# Fpga.net
KiCad netlist of a schematic drawn in Altium Designer
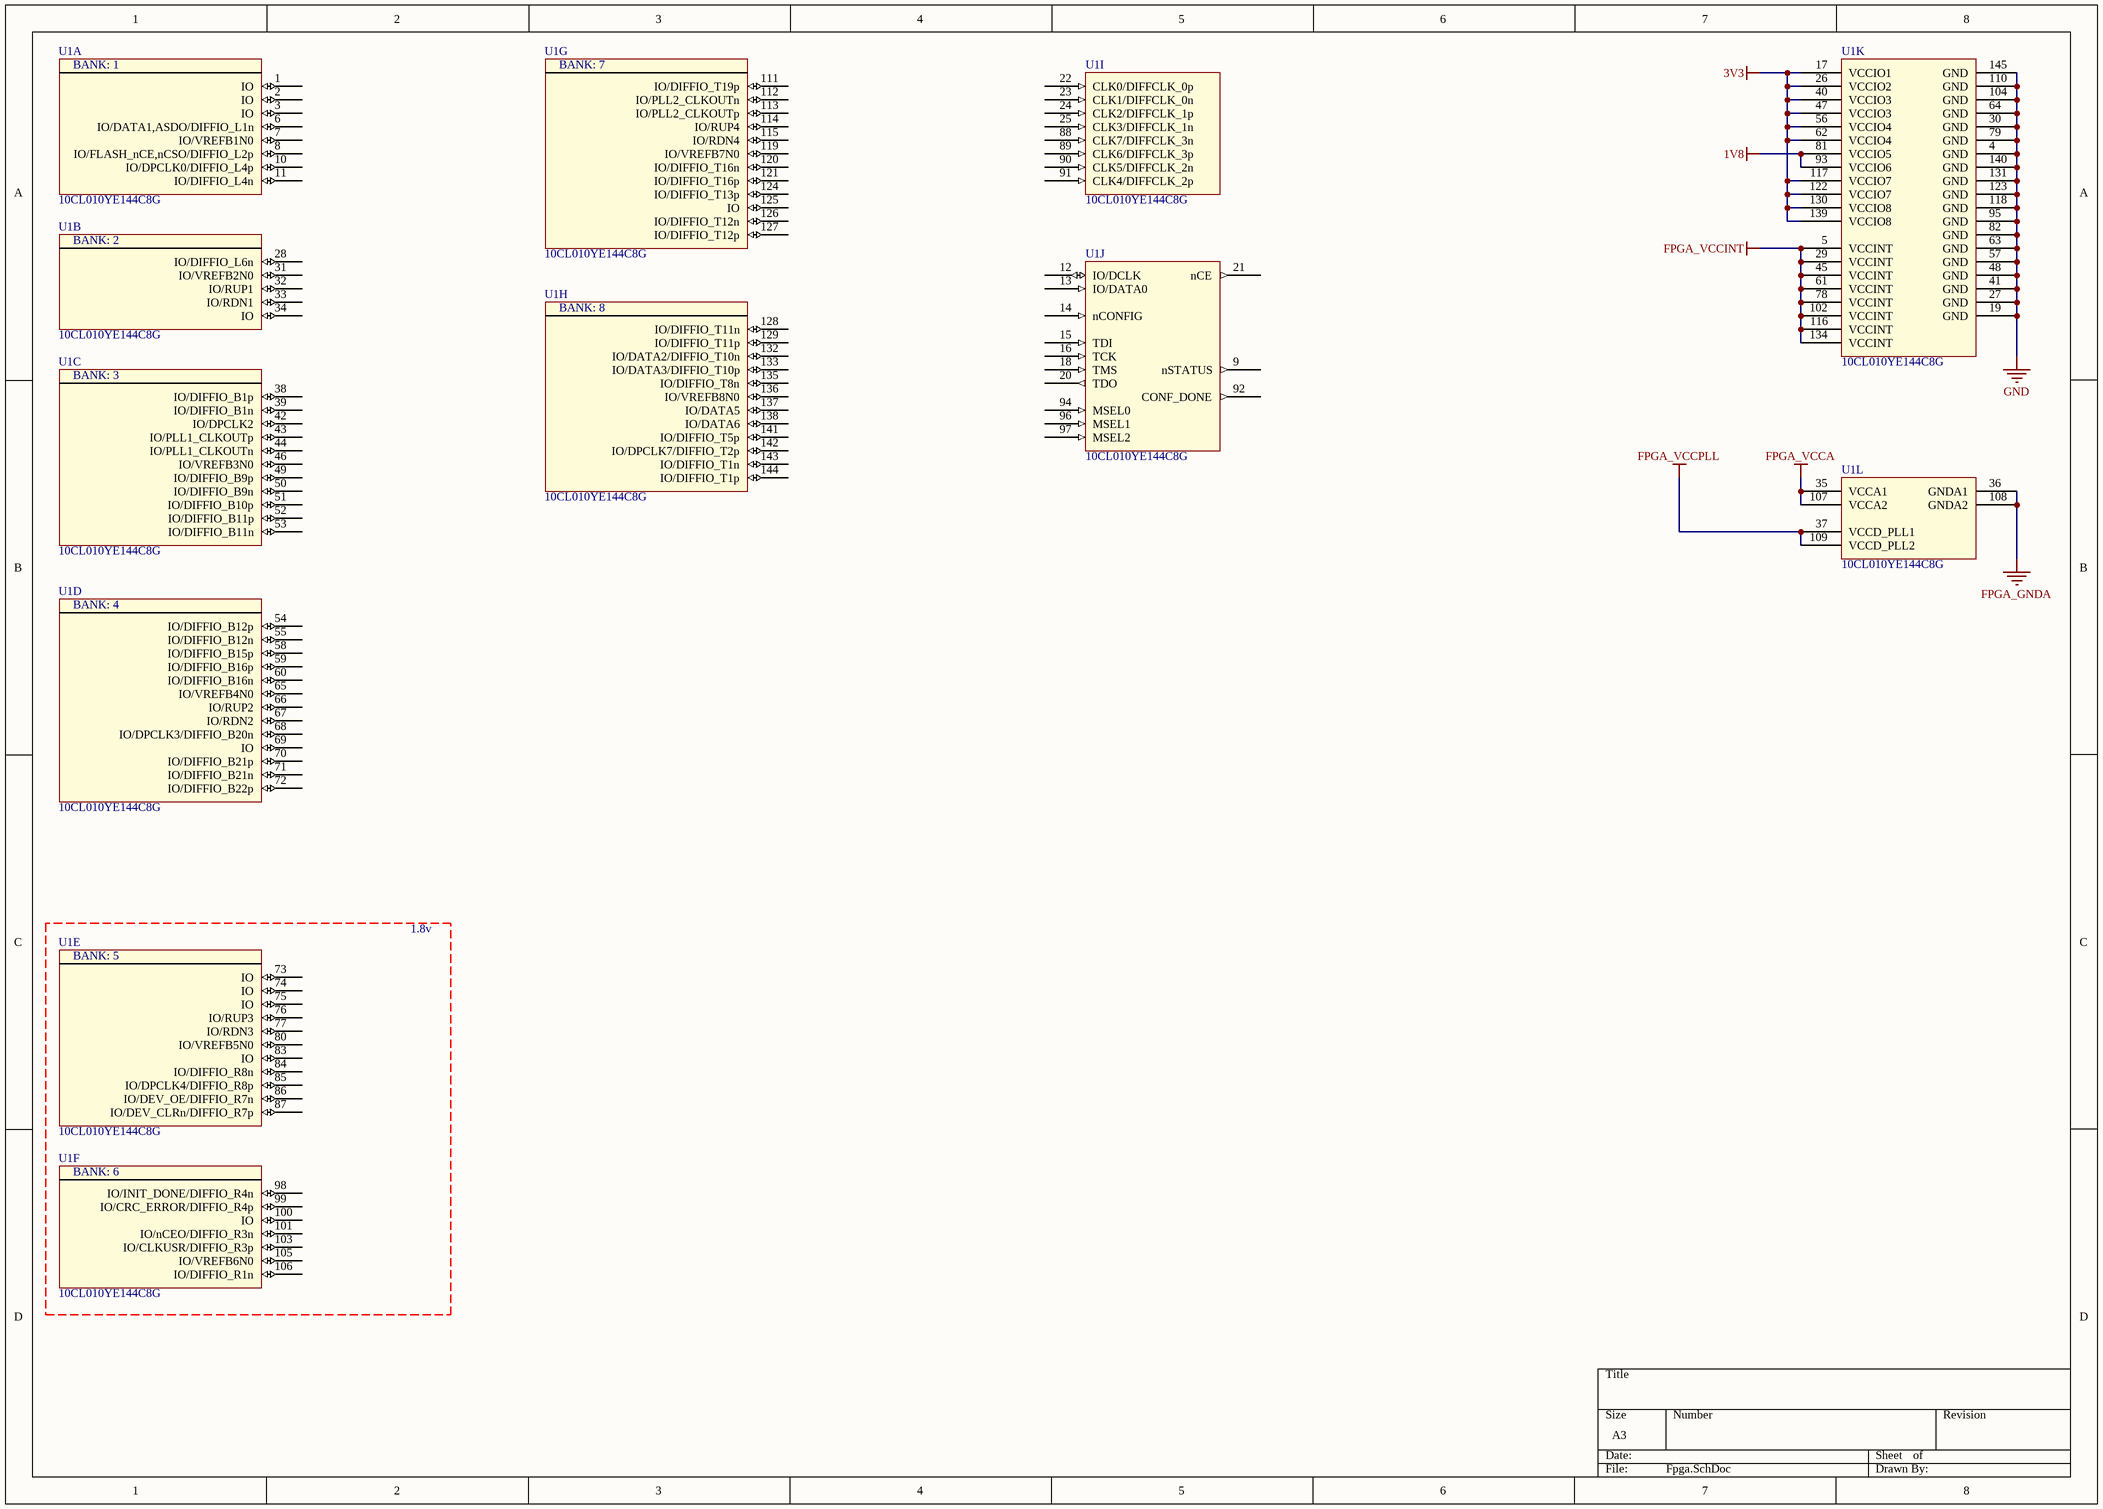
[diagram p0: Fpga.SchDoc]

(export (version "E")
  (design (tool "Eeschema 10.0.6"))
  (components
    (comp (ref "U1")
      (value "10CL010YE144C8G")
      (footprint "Altera TQFP 50P 22X22 145N")
      (description "Intel® Cyclone®10 10CL010 Device")
      (libsource (lib "Schlib") (part "10CL010YE144C8G"))
    )
  )
  (nets
    (net (code "1") (name "1V8") (class "Default")
      (node (ref "U1") (pin "81") (pinfunction "VCCIO5_81") (pintype "power_in"))
      (node (ref "U1") (pin "93") (pinfunction "VCCIO6_93") (pintype "power_in"))
    )
    (net (code "2") (name "3V3") (class "Default")
      (node (ref "U1") (pin "117") (pinfunction "VCCIO7_117") (pintype "power_in"))
      (node (ref "U1") (pin "122") (pinfunction "VCCIO7_122") (pintype "power_in"))
      (node (ref "U1") (pin "130") (pinfunction "VCCIO8_130") (pintype "power_in"))
      (node (ref "U1") (pin "139") (pinfunction "VCCIO8_139") (pintype "power_in"))
      (node (ref "U1") (pin "17") (pinfunction "VCCIO1_17") (pintype "power_in"))
      (node (ref "U1") (pin "26") (pinfunction "VCCIO2_26") (pintype "power_in"))
      (node (ref "U1") (pin "40") (pinfunction "VCCIO3_40") (pintype "power_in"))
      (node (ref "U1") (pin "47") (pinfunction "VCCIO3_47") (pintype "power_in"))
      (node (ref "U1") (pin "56") (pinfunction "VCCIO4_56") (pintype "power_in"))
      (node (ref "U1") (pin "62") (pinfunction "VCCIO4_62") (pintype "power_in"))
    )
    (net (code "3") (name "FPGA_GNDA") (class "Default")
      (node (ref "U1") (pin "108") (pinfunction "GNDA2_108") (pintype "power_in"))
      (node (ref "U1") (pin "36") (pinfunction "GNDA1_36") (pintype "power_in"))
    )
    (net (code "4") (name "FPGA_VCCA") (class "Default")
      (node (ref "U1") (pin "107") (pinfunction "VCCA2_107") (pintype "power_in"))
      (node (ref "U1") (pin "35") (pinfunction "VCCA1_35") (pintype "power_in"))
    )
    (net (code "5") (name "FPGA_VCCINT") (class "Default")
      (node (ref "U1") (pin "102") (pinfunction "VCCINT_102") (pintype "power_in"))
      (node (ref "U1") (pin "116") (pinfunction "VCCINT_116") (pintype "power_in"))
      (node (ref "U1") (pin "134") (pinfunction "VCCINT_134") (pintype "power_in"))
      (node (ref "U1") (pin "29") (pinfunction "VCCINT_29") (pintype "power_in"))
      (node (ref "U1") (pin "45") (pinfunction "VCCINT_45") (pintype "power_in"))
      (node (ref "U1") (pin "5") (pinfunction "VCCINT_5") (pintype "power_in"))
      (node (ref "U1") (pin "61") (pinfunction "VCCINT_61") (pintype "power_in"))
      (node (ref "U1") (pin "78") (pinfunction "VCCINT_78") (pintype "power_in"))
    )
    (net (code "6") (name "FPGA_VCCPLL") (class "Default")
      (node (ref "U1") (pin "109") (pinfunction "VCCD_PLL2_109") (pintype "power_in"))
      (node (ref "U1") (pin "37") (pinfunction "VCCD_PLL1_37") (pintype "power_in"))
    )
    (net (code "7") (name "GND") (class "Default")
      (node (ref "U1") (pin "104") (pinfunction "GND_104") (pintype "power_in"))
      (node (ref "U1") (pin "110") (pinfunction "GND_110") (pintype "power_in"))
      (node (ref "U1") (pin "118") (pinfunction "GND_118") (pintype "power_in"))
      (node (ref "U1") (pin "123") (pinfunction "GND_123") (pintype "power_in"))
      (node (ref "U1") (pin "131") (pinfunction "GND_131") (pintype "power_in"))
      (node (ref "U1") (pin "140") (pinfunction "GND_140") (pintype "power_in"))
      (node (ref "U1") (pin "145") (pinfunction "GND_145") (pintype "power_in"))
      (node (ref "U1") (pin "19") (pinfunction "GND_19") (pintype "power_in"))
      (node (ref "U1") (pin "27") (pinfunction "GND_27") (pintype "power_in"))
      (node (ref "U1") (pin "30") (pinfunction "GND_30") (pintype "power_in"))
      (node (ref "U1") (pin "4") (pinfunction "GND_4") (pintype "power_in"))
      (node (ref "U1") (pin "41") (pinfunction "GND_41") (pintype "power_in"))
      (node (ref "U1") (pin "48") (pinfunction "GND_48") (pintype "power_in"))
      (node (ref "U1") (pin "57") (pinfunction "GND_57") (pintype "power_in"))
      (node (ref "U1") (pin "63") (pinfunction "GND_63") (pintype "power_in"))
      (node (ref "U1") (pin "64") (pinfunction "GND_64") (pintype "power_in"))
      (node (ref "U1") (pin "79") (pinfunction "GND_79") (pintype "power_in"))
      (node (ref "U1") (pin "82") (pinfunction "GND_82") (pintype "power_in"))
      (node (ref "U1") (pin "95") (pinfunction "GND_95") (pintype "power_in"))
    )
    (net (code "8") (name "unconnected-(U1A-IO-Pad1)") (class "Default")
      (node (ref "U1") (pin "1") (pinfunction "IO_1") (pintype "bidirectional"))
    )
    (net (code "9") (name "unconnected-(U1A-IO-Pad2)") (class "Default")
      (node (ref "U1") (pin "2") (pinfunction "IO_2") (pintype "bidirectional"))
    )
    (net (code "10") (name "unconnected-(U1A-IO-Pad3)") (class "Default")
      (node (ref "U1") (pin "3") (pinfunction "IO_3") (pintype "bidirectional"))
    )
    (net (code "11") (name "unconnected-(U1A-IO{slash}DATA1,ASDO{slash}DIFFIO_L1n-Pad6)") (class "Default")
      (node (ref "U1") (pin "6") (pinfunction "IO/DATA1,ASDO/DIFFIO_L1n_6") (pintype "bidirectional"))
    )
    (net (code "12") (name "unconnected-(U1A-IO{slash}DIFFIO_L4n-Pad11)") (class "Default")
      (node (ref "U1") (pin "11") (pinfunction "IO/DIFFIO_L4n_11") (pintype "bidirectional"))
    )
    (net (code "13") (name "unconnected-(U1A-IO{slash}DPCLK0{slash}DIFFIO_L4p-Pad10)") (class "Default")
      (node (ref "U1") (pin "10") (pinfunction "IO/DPCLK0/DIFFIO_L4p_10") (pintype "bidirectional"))
    )
    (net (code "14") (name "unconnected-(U1A-IO{slash}FLASH_nCE,nCSO{slash}DIFFIO_L2p-Pad8)") (class "Default")
      (node (ref "U1") (pin "8") (pinfunction "IO/FLASH_nCE,nCSO/DIFFIO_L2p_8") (pintype "bidirectional"))
    )
    (net (code "15") (name "unconnected-(U1A-IO{slash}VREFB1N0-Pad7)") (class "Default")
      (node (ref "U1") (pin "7") (pinfunction "IO/VREFB1N0_7") (pintype "bidirectional"))
    )
    (net (code "16") (name "unconnected-(U1B-IO-Pad34)") (class "Default")
      (node (ref "U1") (pin "34") (pinfunction "IO_34") (pintype "bidirectional"))
    )
    (net (code "17") (name "unconnected-(U1B-IO{slash}DIFFIO_L6n-Pad28)") (class "Default")
      (node (ref "U1") (pin "28") (pinfunction "IO/DIFFIO_L6n_28") (pintype "bidirectional"))
    )
    (net (code "18") (name "unconnected-(U1B-IO{slash}RDN1-Pad33)") (class "Default")
      (node (ref "U1") (pin "33") (pinfunction "IO/RDN1_33") (pintype "bidirectional"))
    )
    (net (code "19") (name "unconnected-(U1B-IO{slash}RUP1-Pad32)") (class "Default")
      (node (ref "U1") (pin "32") (pinfunction "IO/RUP1_32") (pintype "bidirectional"))
    )
    (net (code "20") (name "unconnected-(U1B-IO{slash}VREFB2N0-Pad31)") (class "Default")
      (node (ref "U1") (pin "31") (pinfunction "IO/VREFB2N0_31") (pintype "bidirectional"))
    )
    (net (code "21") (name "unconnected-(U1C-IO{slash}DIFFIO_B1n-Pad39)") (class "Default")
      (node (ref "U1") (pin "39") (pinfunction "IO/DIFFIO_B1n_39") (pintype "bidirectional"))
    )
    (net (code "22") (name "unconnected-(U1C-IO{slash}DIFFIO_B1p-Pad38)") (class "Default")
      (node (ref "U1") (pin "38") (pinfunction "IO/DIFFIO_B1p_38") (pintype "bidirectional"))
    )
    (net (code "23") (name "unconnected-(U1C-IO{slash}DIFFIO_B9n-Pad50)") (class "Default")
      (node (ref "U1") (pin "50") (pinfunction "IO/DIFFIO_B9n_50") (pintype "bidirectional"))
    )
    (net (code "24") (name "unconnected-(U1C-IO{slash}DIFFIO_B9p-Pad49)") (class "Default")
      (node (ref "U1") (pin "49") (pinfunction "IO/DIFFIO_B9p_49") (pintype "bidirectional"))
    )
    (net (code "25") (name "unconnected-(U1C-IO{slash}DIFFIO_B10p-Pad51)") (class "Default")
      (node (ref "U1") (pin "51") (pinfunction "IO/DIFFIO_B10p_51") (pintype "bidirectional"))
    )
    (net (code "26") (name "unconnected-(U1C-IO{slash}DIFFIO_B11n-Pad53)") (class "Default")
      (node (ref "U1") (pin "53") (pinfunction "IO/DIFFIO_B11n_53") (pintype "bidirectional"))
    )
    (net (code "27") (name "unconnected-(U1C-IO{slash}DIFFIO_B11p-Pad52)") (class "Default")
      (node (ref "U1") (pin "52") (pinfunction "IO/DIFFIO_B11p_52") (pintype "bidirectional"))
    )
    (net (code "28") (name "unconnected-(U1C-IO{slash}DPCLK2-Pad42)") (class "Default")
      (node (ref "U1") (pin "42") (pinfunction "IO/DPCLK2_42") (pintype "bidirectional"))
    )
    (net (code "29") (name "unconnected-(U1C-IO{slash}PLL1_CLKOUTn-Pad44)") (class "Default")
      (node (ref "U1") (pin "44") (pinfunction "IO/PLL1_CLKOUTn_44") (pintype "bidirectional"))
    )
    (net (code "30") (name "unconnected-(U1C-IO{slash}PLL1_CLKOUTp-Pad43)") (class "Default")
      (node (ref "U1") (pin "43") (pinfunction "IO/PLL1_CLKOUTp_43") (pintype "bidirectional"))
    )
    (net (code "31") (name "unconnected-(U1C-IO{slash}VREFB3N0-Pad46)") (class "Default")
      (node (ref "U1") (pin "46") (pinfunction "IO/VREFB3N0_46") (pintype "bidirectional"))
    )
    (net (code "32") (name "unconnected-(U1D-IO-Pad69)") (class "Default")
      (node (ref "U1") (pin "69") (pinfunction "IO_69") (pintype "bidirectional"))
    )
    (net (code "33") (name "unconnected-(U1D-IO{slash}DIFFIO_B12n-Pad55)") (class "Default")
      (node (ref "U1") (pin "55") (pinfunction "IO/DIFFIO_B12n_55") (pintype "bidirectional"))
    )
    (net (code "34") (name "unconnected-(U1D-IO{slash}DIFFIO_B12p-Pad54)") (class "Default")
      (node (ref "U1") (pin "54") (pinfunction "IO/DIFFIO_B12p_54") (pintype "bidirectional"))
    )
    (net (code "35") (name "unconnected-(U1D-IO{slash}DIFFIO_B15p-Pad58)") (class "Default")
      (node (ref "U1") (pin "58") (pinfunction "IO/DIFFIO_B15p_58") (pintype "bidirectional"))
    )
    (net (code "36") (name "unconnected-(U1D-IO{slash}DIFFIO_B16n-Pad60)") (class "Default")
      (node (ref "U1") (pin "60") (pinfunction "IO/DIFFIO_B16n_60") (pintype "bidirectional"))
    )
    (net (code "37") (name "unconnected-(U1D-IO{slash}DIFFIO_B16p-Pad59)") (class "Default")
      (node (ref "U1") (pin "59") (pinfunction "IO/DIFFIO_B16p_59") (pintype "bidirectional"))
    )
    (net (code "38") (name "unconnected-(U1D-IO{slash}DIFFIO_B21n-Pad71)") (class "Default")
      (node (ref "U1") (pin "71") (pinfunction "IO/DIFFIO_B21n_71") (pintype "bidirectional"))
    )
    (net (code "39") (name "unconnected-(U1D-IO{slash}DIFFIO_B21p-Pad70)") (class "Default")
      (node (ref "U1") (pin "70") (pinfunction "IO/DIFFIO_B21p_70") (pintype "bidirectional"))
    )
    (net (code "40") (name "unconnected-(U1D-IO{slash}DIFFIO_B22p-Pad72)") (class "Default")
      (node (ref "U1") (pin "72") (pinfunction "IO/DIFFIO_B22p_72") (pintype "bidirectional"))
    )
    (net (code "41") (name "unconnected-(U1D-IO{slash}DPCLK3{slash}DIFFIO_B20n-Pad68)") (class "Default")
      (node (ref "U1") (pin "68") (pinfunction "IO/DPCLK3/DIFFIO_B20n_68") (pintype "bidirectional"))
    )
    (net (code "42") (name "unconnected-(U1D-IO{slash}RDN2-Pad67)") (class "Default")
      (node (ref "U1") (pin "67") (pinfunction "IO/RDN2_67") (pintype "bidirectional"))
    )
    (net (code "43") (name "unconnected-(U1D-IO{slash}RUP2-Pad66)") (class "Default")
      (node (ref "U1") (pin "66") (pinfunction "IO/RUP2_66") (pintype "bidirectional"))
    )
    (net (code "44") (name "unconnected-(U1D-IO{slash}VREFB4N0-Pad65)") (class "Default")
      (node (ref "U1") (pin "65") (pinfunction "IO/VREFB4N0_65") (pintype "bidirectional"))
    )
    (net (code "45") (name "unconnected-(U1E-IO-Pad73)") (class "Default")
      (node (ref "U1") (pin "73") (pinfunction "IO_73") (pintype "bidirectional"))
    )
    (net (code "46") (name "unconnected-(U1E-IO-Pad74)") (class "Default")
      (node (ref "U1") (pin "74") (pinfunction "IO_74") (pintype "bidirectional"))
    )
    (net (code "47") (name "unconnected-(U1E-IO-Pad75)") (class "Default")
      (node (ref "U1") (pin "75") (pinfunction "IO_75") (pintype "bidirectional"))
    )
    (net (code "48") (name "unconnected-(U1E-IO-Pad83)") (class "Default")
      (node (ref "U1") (pin "83") (pinfunction "IO_83") (pintype "bidirectional"))
    )
    (net (code "49") (name "unconnected-(U1E-IO{slash}DEV_CLRn{slash}DIFFIO_R7p-Pad87)") (class "Default")
      (node (ref "U1") (pin "87") (pinfunction "IO/DEV_CLRn/DIFFIO_R7p_87") (pintype "bidirectional"))
    )
    (net (code "50") (name "unconnected-(U1E-IO{slash}DEV_OE{slash}DIFFIO_R7n-Pad86)") (class "Default")
      (node (ref "U1") (pin "86") (pinfunction "IO/DEV_OE/DIFFIO_R7n_86") (pintype "bidirectional"))
    )
    (net (code "51") (name "unconnected-(U1E-IO{slash}DIFFIO_R8n-Pad84)") (class "Default")
      (node (ref "U1") (pin "84") (pinfunction "IO/DIFFIO_R8n_84") (pintype "bidirectional"))
    )
    (net (code "52") (name "unconnected-(U1E-IO{slash}DPCLK4{slash}DIFFIO_R8p-Pad85)") (class "Default")
      (node (ref "U1") (pin "85") (pinfunction "IO/DPCLK4/DIFFIO_R8p_85") (pintype "bidirectional"))
    )
    (net (code "53") (name "unconnected-(U1E-IO{slash}RDN3-Pad77)") (class "Default")
      (node (ref "U1") (pin "77") (pinfunction "IO/RDN3_77") (pintype "bidirectional"))
    )
    (net (code "54") (name "unconnected-(U1E-IO{slash}RUP3-Pad76)") (class "Default")
      (node (ref "U1") (pin "76") (pinfunction "IO/RUP3_76") (pintype "bidirectional"))
    )
    (net (code "55") (name "unconnected-(U1E-IO{slash}VREFB5N0-Pad80)") (class "Default")
      (node (ref "U1") (pin "80") (pinfunction "IO/VREFB5N0_80") (pintype "bidirectional"))
    )
    (net (code "56") (name "unconnected-(U1F-IO-Pad100)") (class "Default")
      (node (ref "U1") (pin "100") (pinfunction "IO_100") (pintype "bidirectional"))
    )
    (net (code "57") (name "unconnected-(U1F-IO{slash}CLKUSR{slash}DIFFIO_R3p-Pad103)") (class "Default")
      (node (ref "U1") (pin "103") (pinfunction "IO/CLKUSR/DIFFIO_R3p_103") (pintype "bidirectional"))
    )
    (net (code "58") (name "unconnected-(U1F-IO{slash}CRC_ERROR{slash}DIFFIO_R4p-Pad99)") (class "Default")
      (node (ref "U1") (pin "99") (pinfunction "IO/CRC_ERROR/DIFFIO_R4p_99") (pintype "bidirectional"))
    )
    (net (code "59") (name "unconnected-(U1F-IO{slash}DIFFIO_R1n-Pad106)") (class "Default")
      (node (ref "U1") (pin "106") (pinfunction "IO/DIFFIO_R1n_106") (pintype "bidirectional"))
    )
    (net (code "60") (name "unconnected-(U1F-IO{slash}INIT_DONE{slash}DIFFIO_R4n-Pad98)") (class "Default")
      (node (ref "U1") (pin "98") (pinfunction "IO/INIT_DONE/DIFFIO_R4n_98") (pintype "bidirectional"))
    )
    (net (code "61") (name "unconnected-(U1F-IO{slash}VREFB6N0-Pad105)") (class "Default")
      (node (ref "U1") (pin "105") (pinfunction "IO/VREFB6N0_105") (pintype "bidirectional"))
    )
    (net (code "62") (name "unconnected-(U1F-IO{slash}nCEO{slash}DIFFIO_R3n-Pad101)") (class "Default")
      (node (ref "U1") (pin "101") (pinfunction "IO/nCEO/DIFFIO_R3n_101") (pintype "bidirectional"))
    )
    (net (code "63") (name "unconnected-(U1G-IO-Pad125)") (class "Default")
      (node (ref "U1") (pin "125") (pinfunction "IO_125") (pintype "bidirectional"))
    )
    (net (code "64") (name "unconnected-(U1G-IO{slash}DIFFIO_T12n-Pad126)") (class "Default")
      (node (ref "U1") (pin "126") (pinfunction "IO/DIFFIO_T12n_126") (pintype "bidirectional"))
    )
    (net (code "65") (name "unconnected-(U1G-IO{slash}DIFFIO_T12p-Pad127)") (class "Default")
      (node (ref "U1") (pin "127") (pinfunction "IO/DIFFIO_T12p_127") (pintype "bidirectional"))
    )
    (net (code "66") (name "unconnected-(U1G-IO{slash}DIFFIO_T13p-Pad124)") (class "Default")
      (node (ref "U1") (pin "124") (pinfunction "IO/DIFFIO_T13p_124") (pintype "bidirectional"))
    )
    (net (code "67") (name "unconnected-(U1G-IO{slash}DIFFIO_T16n-Pad120)") (class "Default")
      (node (ref "U1") (pin "120") (pinfunction "IO/DIFFIO_T16n_120") (pintype "bidirectional"))
    )
    (net (code "68") (name "unconnected-(U1G-IO{slash}DIFFIO_T16p-Pad121)") (class "Default")
      (node (ref "U1") (pin "121") (pinfunction "IO/DIFFIO_T16p_121") (pintype "bidirectional"))
    )
    (net (code "69") (name "unconnected-(U1G-IO{slash}DIFFIO_T19p-Pad111)") (class "Default")
      (node (ref "U1") (pin "111") (pinfunction "IO/DIFFIO_T19p_111") (pintype "bidirectional"))
    )
    (net (code "70") (name "unconnected-(U1G-IO{slash}PLL2_CLKOUTn-Pad112)") (class "Default")
      (node (ref "U1") (pin "112") (pinfunction "IO/PLL2_CLKOUTn_112") (pintype "bidirectional"))
    )
    (net (code "71") (name "unconnected-(U1G-IO{slash}PLL2_CLKOUTp-Pad113)") (class "Default")
      (node (ref "U1") (pin "113") (pinfunction "IO/PLL2_CLKOUTp_113") (pintype "bidirectional"))
    )
    (net (code "72") (name "unconnected-(U1G-IO{slash}RDN4-Pad115)") (class "Default")
      (node (ref "U1") (pin "115") (pinfunction "IO/RDN4_115") (pintype "bidirectional"))
    )
    (net (code "73") (name "unconnected-(U1G-IO{slash}RUP4-Pad114)") (class "Default")
      (node (ref "U1") (pin "114") (pinfunction "IO/RUP4_114") (pintype "bidirectional"))
    )
    (net (code "74") (name "unconnected-(U1G-IO{slash}VREFB7N0-Pad119)") (class "Default")
      (node (ref "U1") (pin "119") (pinfunction "IO/VREFB7N0_119") (pintype "bidirectional"))
    )
    (net (code "75") (name "unconnected-(U1H-IO{slash}DATA2{slash}DIFFIO_T10n-Pad132)") (class "Default")
      (node (ref "U1") (pin "132") (pinfunction "IO/DATA2/DIFFIO_T10n_132") (pintype "bidirectional"))
    )
    (net (code "76") (name "unconnected-(U1H-IO{slash}DATA3{slash}DIFFIO_T10p-Pad133)") (class "Default")
      (node (ref "U1") (pin "133") (pinfunction "IO/DATA3/DIFFIO_T10p_133") (pintype "bidirectional"))
    )
    (net (code "77") (name "unconnected-(U1H-IO{slash}DATA5-Pad137)") (class "Default")
      (node (ref "U1") (pin "137") (pinfunction "IO/DATA5_137") (pintype "bidirectional"))
    )
    (net (code "78") (name "unconnected-(U1H-IO{slash}DATA6-Pad138)") (class "Default")
      (node (ref "U1") (pin "138") (pinfunction "IO/DATA6_138") (pintype "bidirectional"))
    )
    (net (code "79") (name "unconnected-(U1H-IO{slash}DIFFIO_T1n-Pad143)") (class "Default")
      (node (ref "U1") (pin "143") (pinfunction "IO/DIFFIO_T1n_143") (pintype "bidirectional"))
    )
    (net (code "80") (name "unconnected-(U1H-IO{slash}DIFFIO_T1p-Pad144)") (class "Default")
      (node (ref "U1") (pin "144") (pinfunction "IO/DIFFIO_T1p_144") (pintype "bidirectional"))
    )
    (net (code "81") (name "unconnected-(U1H-IO{slash}DIFFIO_T5p-Pad141)") (class "Default")
      (node (ref "U1") (pin "141") (pinfunction "IO/DIFFIO_T5p_141") (pintype "bidirectional"))
    )
    (net (code "82") (name "unconnected-(U1H-IO{slash}DIFFIO_T8n-Pad135)") (class "Default")
      (node (ref "U1") (pin "135") (pinfunction "IO/DIFFIO_T8n_135") (pintype "bidirectional"))
    )
    (net (code "83") (name "unconnected-(U1H-IO{slash}DIFFIO_T11n-Pad128)") (class "Default")
      (node (ref "U1") (pin "128") (pinfunction "IO/DIFFIO_T11n_128") (pintype "bidirectional"))
    )
    (net (code "84") (name "unconnected-(U1H-IO{slash}DIFFIO_T11p-Pad129)") (class "Default")
      (node (ref "U1") (pin "129") (pinfunction "IO/DIFFIO_T11p_129") (pintype "bidirectional"))
    )
    (net (code "85") (name "unconnected-(U1H-IO{slash}DPCLK7{slash}DIFFIO_T2p-Pad142)") (class "Default")
      (node (ref "U1") (pin "142") (pinfunction "IO/DPCLK7/DIFFIO_T2p_142") (pintype "bidirectional"))
    )
    (net (code "86") (name "unconnected-(U1H-IO{slash}VREFB8N0-Pad136)") (class "Default")
      (node (ref "U1") (pin "136") (pinfunction "IO/VREFB8N0_136") (pintype "bidirectional"))
    )
    (net (code "87") (name "unconnected-(U1I-CLK0{slash}DIFFCLK_0p-Pad22)") (class "Default")
      (node (ref "U1") (pin "22") (pinfunction "CLK0/DIFFCLK_0p_22") (pintype "input"))
    )
    (net (code "88") (name "unconnected-(U1I-CLK1{slash}DIFFCLK_0n-Pad23)") (class "Default")
      (node (ref "U1") (pin "23") (pinfunction "CLK1/DIFFCLK_0n_23") (pintype "input"))
    )
    (net (code "89") (name "unconnected-(U1I-CLK2{slash}DIFFCLK_1p-Pad24)") (class "Default")
      (node (ref "U1") (pin "24") (pinfunction "CLK2/DIFFCLK_1p_24") (pintype "input"))
    )
    (net (code "90") (name "unconnected-(U1I-CLK3{slash}DIFFCLK_1n-Pad25)") (class "Default")
      (node (ref "U1") (pin "25") (pinfunction "CLK3/DIFFCLK_1n_25") (pintype "input"))
    )
    (net (code "91") (name "unconnected-(U1I-CLK4{slash}DIFFCLK_2p-Pad91)") (class "Default")
      (node (ref "U1") (pin "91") (pinfunction "CLK4/DIFFCLK_2p_91") (pintype "input"))
    )
    (net (code "92") (name "unconnected-(U1I-CLK5{slash}DIFFCLK_2n-Pad90)") (class "Default")
      (node (ref "U1") (pin "90") (pinfunction "CLK5/DIFFCLK_2n_90") (pintype "input"))
    )
    (net (code "93") (name "unconnected-(U1I-CLK6{slash}DIFFCLK_3p-Pad89)") (class "Default")
      (node (ref "U1") (pin "89") (pinfunction "CLK6/DIFFCLK_3p_89") (pintype "input"))
    )
    (net (code "94") (name "unconnected-(U1I-CLK7{slash}DIFFCLK_3n-Pad88)") (class "Default")
      (node (ref "U1") (pin "88") (pinfunction "CLK7/DIFFCLK_3n_88") (pintype "input"))
    )
    (net (code "95") (name "unconnected-(U1J-CONF_DONE-Pad92)") (class "Default")
      (node (ref "U1") (pin "92") (pinfunction "CONF_DONE_92") (pintype "output"))
    )
    (net (code "96") (name "unconnected-(U1J-IO{slash}DATA0-Pad13)") (class "Default")
      (node (ref "U1") (pin "13") (pinfunction "IO/DATA0_13") (pintype "input"))
    )
    (net (code "97") (name "unconnected-(U1J-IO{slash}DCLK-Pad12)") (class "Default")
      (node (ref "U1") (pin "12") (pinfunction "IO/DCLK_12") (pintype "bidirectional"))
    )
    (net (code "98") (name "unconnected-(U1J-MSEL0-Pad94)") (class "Default")
      (node (ref "U1") (pin "94") (pinfunction "MSEL0_94") (pintype "input"))
    )
    (net (code "99") (name "unconnected-(U1J-MSEL1-Pad96)") (class "Default")
      (node (ref "U1") (pin "96") (pinfunction "MSEL1_96") (pintype "input"))
    )
    (net (code "100") (name "unconnected-(U1J-MSEL2-Pad97)") (class "Default")
      (node (ref "U1") (pin "97") (pinfunction "MSEL2_97") (pintype "input"))
    )
    (net (code "101") (name "unconnected-(U1J-TCK-Pad16)") (class "Default")
      (node (ref "U1") (pin "16") (pinfunction "TCK_16") (pintype "input"))
    )
    (net (code "102") (name "unconnected-(U1J-TDI-Pad15)") (class "Default")
      (node (ref "U1") (pin "15") (pinfunction "TDI_15") (pintype "input"))
    )
    (net (code "103") (name "unconnected-(U1J-TDO-Pad20)") (class "Default")
      (node (ref "U1") (pin "20") (pinfunction "TDO_20") (pintype "output"))
    )
    (net (code "104") (name "unconnected-(U1J-TMS-Pad18)") (class "Default")
      (node (ref "U1") (pin "18") (pinfunction "TMS_18") (pintype "input"))
    )
    (net (code "105") (name "unconnected-(U1J-nCE-Pad21)") (class "Default")
      (node (ref "U1") (pin "21") (pinfunction "nCE_21") (pintype "output"))
    )
    (net (code "106") (name "unconnected-(U1J-nCONFIG-Pad14)") (class "Default")
      (node (ref "U1") (pin "14") (pinfunction "nCONFIG_14") (pintype "input"))
    )
    (net (code "107") (name "unconnected-(U1J-nSTATUS-Pad9)") (class "Default")
      (node (ref "U1") (pin "9") (pinfunction "nSTATUS_9") (pintype "output"))
    )
  )
)
